# v0_4_2.net
KiCad netlist of a schematic drawn in EAGLE
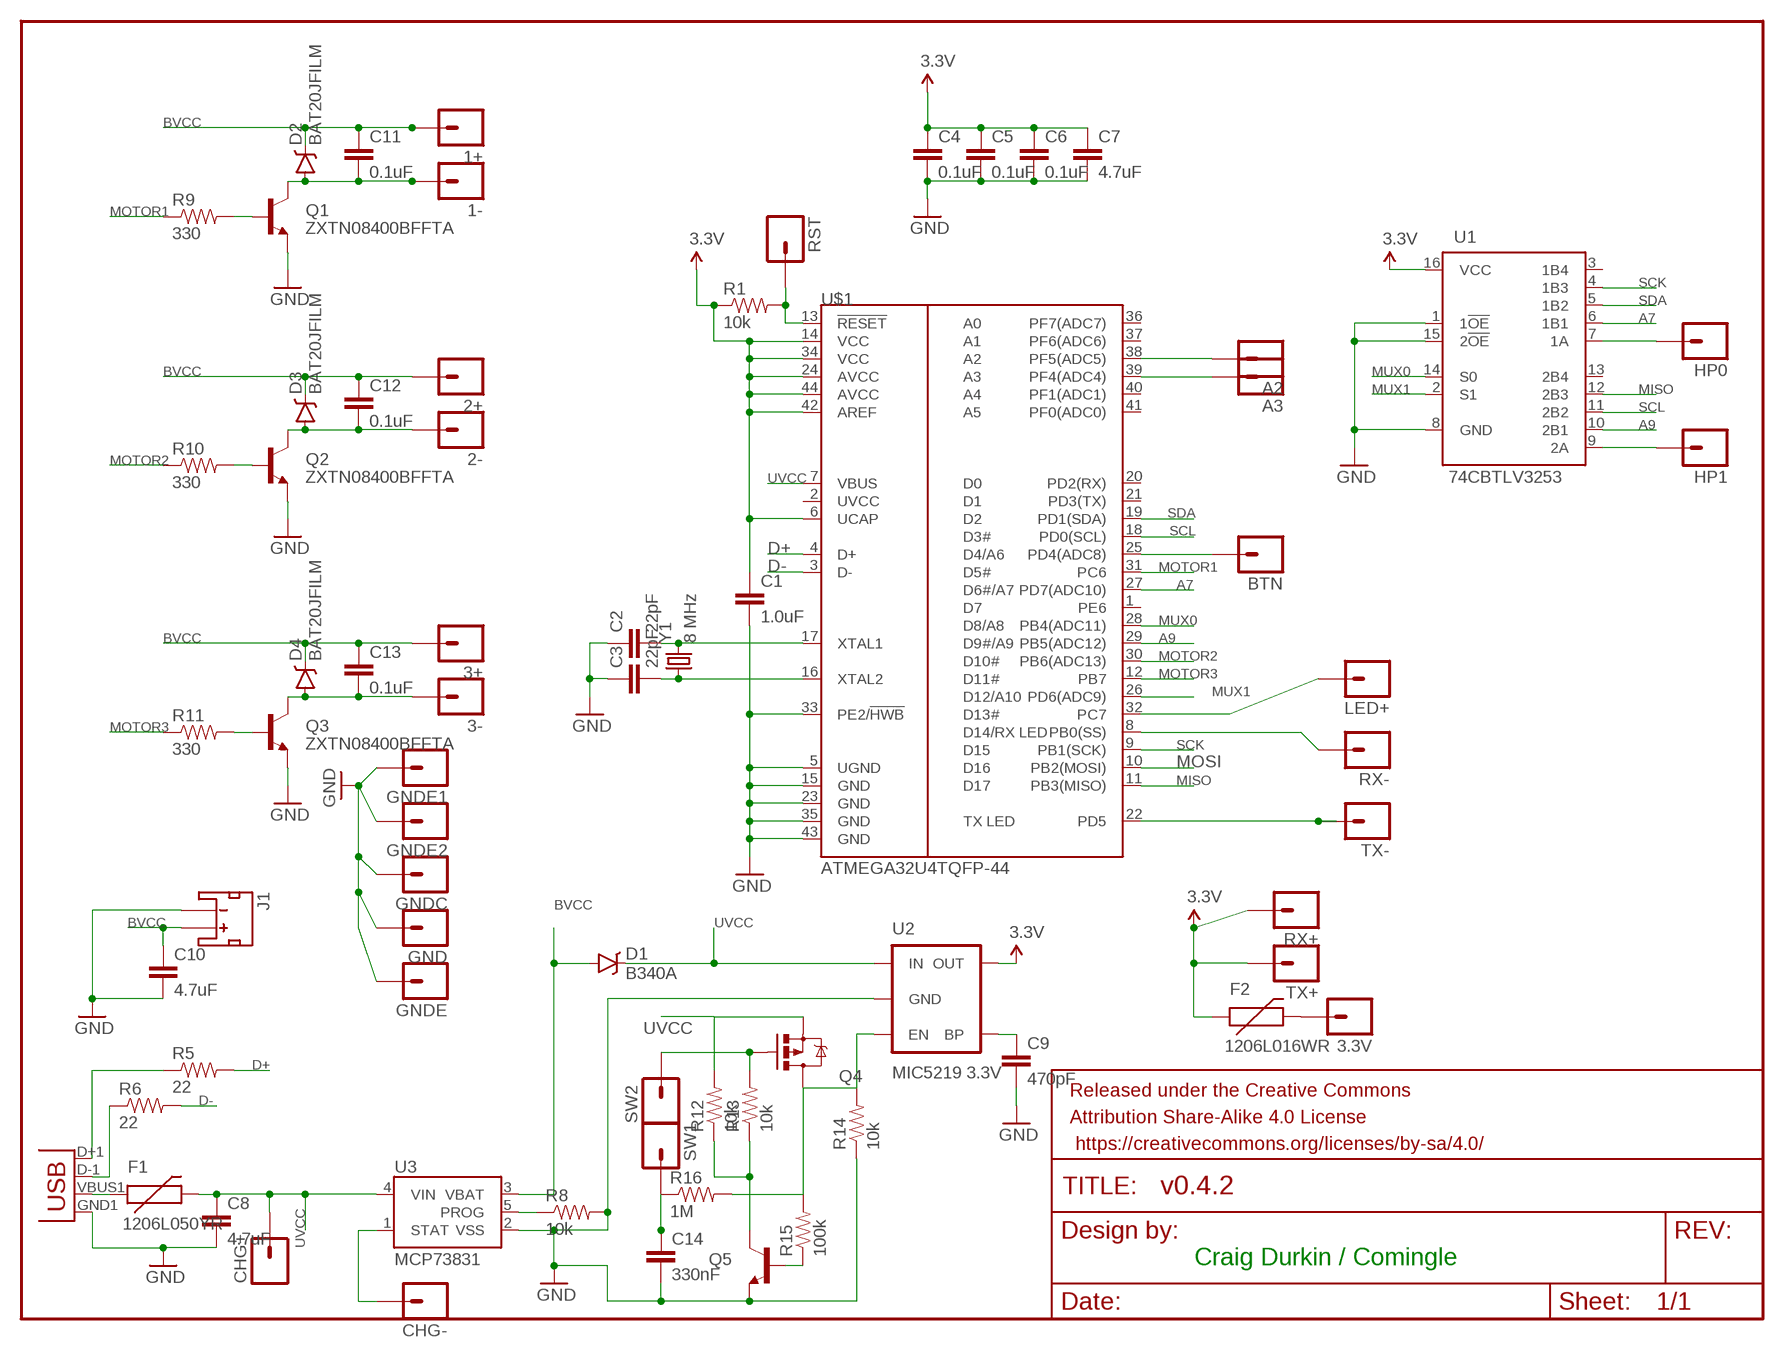
[diagram p0: schematic, sheet 1]

(export (version "E")
  (design (tool "Eeschema 10.0.6"))
  (components
    (comp (ref "1+")
      (value "M01PTH")
      (footprint "eagle-import:1X01")
      (libsource (lib "eagle-import") (part "M01PTH"))
    )
    (comp (ref "1-")
      (value "M01PTH")
      (footprint "eagle-import:1X01")
      (libsource (lib "eagle-import") (part "M01PTH"))
    )
    (comp (ref "2+")
      (value "M01PTH")
      (footprint "eagle-import:1X01")
      (libsource (lib "eagle-import") (part "M01PTH"))
    )
    (comp (ref "2-")
      (value "M01PTH")
      (footprint "eagle-import:1X01")
      (libsource (lib "eagle-import") (part "M01PTH"))
    )
    (comp (ref "3+")
      (value "M01PTH")
      (footprint "eagle-import:1X01")
      (libsource (lib "eagle-import") (part "M01PTH"))
    )
    (comp (ref "3-")
      (value "M01PTH")
      (footprint "eagle-import:1X01")
      (libsource (lib "eagle-import") (part "M01PTH"))
    )
    (comp (ref "3.3V")
      (value "M01PTH")
      (footprint "eagle-import:1X01")
      (libsource (lib "eagle-import") (part "M01PTH"))
    )
    (comp (ref "A2")
      (value "M01PTH")
      (footprint "eagle-import:1X01")
      (libsource (lib "eagle-import") (part "M01PTH"))
    )
    (comp (ref "A3")
      (value "M01PTH")
      (footprint "eagle-import:1X01")
      (libsource (lib "eagle-import") (part "M01PTH"))
    )
    (comp (ref "BTN")
      (value "M01PTH")
      (footprint "eagle-import:1X01")
      (libsource (lib "eagle-import") (part "M01PTH"))
    )
    (comp (ref "C1")
      (value "1.0uF")
      (footprint "eagle-import:0603-CAP")
      (libsource (lib "eagle-import") (part "CAP0603-CAP"))
    )
    (comp (ref "C2")
      (value "22pF")
      (footprint "eagle-import:0603-CAP")
      (libsource (lib "eagle-import") (part "CAP0603-CAP"))
    )
    (comp (ref "C3")
      (value "22pF")
      (footprint "eagle-import:0603-CAP")
      (libsource (lib "eagle-import") (part "CAP0603-CAP"))
    )
    (comp (ref "C4")
      (value "0.1uF")
      (footprint "eagle-import:0603-CAP")
      (libsource (lib "eagle-import") (part "SparkFun-Passives_CAP0603-CAP"))
    )
    (comp (ref "C5")
      (value "0.1uF")
      (footprint "eagle-import:0603-CAP")
      (libsource (lib "eagle-import") (part "SparkFun-Passives_CAP0603-CAP"))
    )
    (comp (ref "C6")
      (value "0.1uF")
      (footprint "eagle-import:0603-CAP")
      (libsource (lib "eagle-import") (part "SparkFun-Passives_CAP0603-CAP"))
    )
    (comp (ref "C7")
      (value "4.7uF")
      (footprint "eagle-import:0603-CAP")
      (libsource (lib "eagle-import") (part "SparkFun-Passives_CAP0603-CAP"))
    )
    (comp (ref "C8")
      (value "4.7uF")
      (footprint "eagle-import:1206")
      (libsource (lib "eagle-import") (part "SparkFun-Passives_CAP1206"))
    )
    (comp (ref "C9")
      (value "470pF")
      (footprint "eagle-import:0603-CAP")
      (libsource (lib "eagle-import") (part "CAP0603-CAP"))
    )
    (comp (ref "C10")
      (value "4.7uF")
      (footprint "eagle-import:1206")
      (libsource (lib "eagle-import") (part "SparkFun-Passives_CAP1206"))
    )
    (comp (ref "C11")
      (value "0.1uF")
      (footprint "eagle-import:0603-CAP")
      (libsource (lib "eagle-import") (part "CAP0603-CAP"))
    )
    (comp (ref "C12")
      (value "0.1uF")
      (footprint "eagle-import:0603-CAP")
      (libsource (lib "eagle-import") (part "CAP0603-CAP"))
    )
    (comp (ref "C13")
      (value "0.1uF")
      (footprint "eagle-import:0603-CAP")
      (libsource (lib "eagle-import") (part "CAP0603-CAP"))
    )
    (comp (ref "C14")
      (value "330nF")
      (footprint "eagle-import:0603-CAP")
      (libsource (lib "eagle-import") (part "CAP0603-CAP"))
    )
    (comp (ref "CHG+")
      (value "M01PTH")
      (footprint "eagle-import:1X01")
      (libsource (lib "eagle-import") (part "M01PTH"))
    )
    (comp (ref "CHG-")
      (value "M01PTH")
      (footprint "eagle-import:1X01")
      (libsource (lib "eagle-import") (part "M01PTH"))
    )
    (comp (ref "D1")
      (value "B340A")
      (footprint "eagle-import:SMA-DIODE")
      (libsource (lib "eagle-import") (part "DIODE-SCHOTTKY-B340A"))
    )
    (comp (ref "D2")
      (value "BAT20JFILM")
      (footprint "eagle-import:SOD-323")
      (libsource (lib "eagle-import") (part "BAT20JFILM"))
    )
    (comp (ref "D3")
      (value "BAT20JFILM")
      (footprint "eagle-import:SOD-323")
      (libsource (lib "eagle-import") (part "BAT20JFILM"))
    )
    (comp (ref "D4")
      (value "BAT20JFILM")
      (footprint "eagle-import:SOD-323")
      (libsource (lib "eagle-import") (part "BAT20JFILM"))
    )
    (comp (ref "F1")
      (value "1206L050YR")
      (footprint "eagle-import:PTC-1206")
      (libsource (lib "eagle-import") (part "PTCSMD"))
    )
    (comp (ref "F2")
      (value "1206L016WR")
      (footprint "eagle-import:PTC-1206")
      (libsource (lib "eagle-import") (part "PTCSMD"))
    )
    (comp (ref "FRAME1")
      (value "FRAME-LETTER")
      (footprint "eagle-import:CREATIVE_COMMONS")
      (libsource (lib "eagle-import") (part "FRAME-LETTER"))
    )
    (comp (ref "GND")
      (value "M01PTH")
      (footprint "eagle-import:1X01")
      (libsource (lib "eagle-import") (part "M01PTH"))
    )
    (comp (ref "GNDC")
      (value "M01PTH")
      (footprint "eagle-import:1X01")
      (libsource (lib "eagle-import") (part "M01PTH"))
    )
    (comp (ref "GNDE")
      (value "M01PTH")
      (footprint "eagle-import:1X01")
      (libsource (lib "eagle-import") (part "M01PTH"))
    )
    (comp (ref "GNDE1")
      (value "M01PTH")
      (footprint "eagle-import:1X01")
      (libsource (lib "eagle-import") (part "M01PTH"))
    )
    (comp (ref "GNDE2")
      (value "M01PTH")
      (footprint "eagle-import:1X01")
      (libsource (lib "eagle-import") (part "M01PTH"))
    )
    (comp (ref "HP0")
      (value "M01PTH")
      (footprint "eagle-import:1X01")
      (libsource (lib "eagle-import") (part "M01PTH"))
    )
    (comp (ref "HP1")
      (value "M01PTH")
      (footprint "eagle-import:1X01")
      (libsource (lib "eagle-import") (part "M01PTH"))
    )
    (comp (ref "J1")
      (value "JST_2MM_MALE")
      (footprint "eagle-import:JST-2-SMD")
      (libsource (lib "eagle-import") (part "JST_2MM_MALE"))
    )
    (comp (ref "JP4")
      (value "USB")
      (footprint "eagle-import:USB-B-MICRO-SMD_V03")
      (libsource (lib "eagle-import") (part "USB"))
    )
    (comp (ref "LED+")
      (value "M01PTH")
      (footprint "eagle-import:1X01")
      (libsource (lib "eagle-import") (part "M01PTH"))
    )
    (comp (ref "Q1")
      (value "ZXTN08400BFFTA")
      (footprint "eagle-import:SOT23-3")
      (libsource (lib "eagle-import") (part "TRANSISTOR_NPNSOT23-3"))
    )
    (comp (ref "Q2")
      (value "ZXTN08400BFFTA")
      (footprint "eagle-import:SOT23-3")
      (libsource (lib "eagle-import") (part "TRANSISTOR_NPNSOT23-3"))
    )
    (comp (ref "Q3")
      (value "ZXTN08400BFFTA")
      (footprint "eagle-import:SOT23-3")
      (libsource (lib "eagle-import") (part "TRANSISTOR_NPNSOT23-3"))
    )
    (comp (ref "Q4")
      (value "NTS2101PT1G")
      (footprint "eagle-import:SOT23-3")
      (libsource (lib "eagle-import") (part "MOSFET-PCHANNEL"))
    )
    (comp (ref "Q5")
      (value "MMBT2222A")
      (footprint "eagle-import:SOT23-3")
      (libsource (lib "eagle-import") (part "TRANSISTOR_NPNMMBT2222A"))
    )
    (comp (ref "R1")
      (value "10k")
      (footprint "eagle-import:0603-RES")
      (libsource (lib "eagle-import") (part "RESISTOR0603-RES"))
    )
    (comp (ref "R5")
      (value "22")
      (footprint "eagle-import:0603-RES")
      (libsource (lib "eagle-import") (part "RESISTOR0603-RES"))
    )
    (comp (ref "R6")
      (value "22")
      (footprint "eagle-import:0603-RES")
      (libsource (lib "eagle-import") (part "RESISTOR0603-RES"))
    )
    (comp (ref "R8")
      (value "10k")
      (footprint "eagle-import:0603-RES")
      (libsource (lib "eagle-import") (part "RESISTOR0603-RES"))
    )
    (comp (ref "R9")
      (value "330")
      (footprint "eagle-import:0603-RES")
      (libsource (lib "eagle-import") (part "RESISTOR0603-RES"))
    )
    (comp (ref "R10")
      (value "330")
      (footprint "eagle-import:0603-RES")
      (libsource (lib "eagle-import") (part "RESISTOR0603-RES"))
    )
    (comp (ref "R11")
      (value "330")
      (footprint "eagle-import:0603-RES")
      (libsource (lib "eagle-import") (part "RESISTOR0603-RES"))
    )
    (comp (ref "R12")
      (value "10k")
      (footprint "eagle-import:0603-RES")
      (libsource (lib "eagle-import") (part "RESISTOR0603-RES"))
    )
    (comp (ref "R13")
      (value "10k")
      (footprint "eagle-import:0603-RES")
      (libsource (lib "eagle-import") (part "RESISTOR0603-RES"))
    )
    (comp (ref "R14")
      (value "10k")
      (footprint "eagle-import:0603-RES")
      (libsource (lib "eagle-import") (part "RESISTOR0603-RES"))
    )
    (comp (ref "R15")
      (value "100k")
      (footprint "eagle-import:0603-RES")
      (libsource (lib "eagle-import") (part "RESISTOR0603-RES"))
    )
    (comp (ref "R16")
      (value "1M")
      (footprint "eagle-import:0603-RES")
      (libsource (lib "eagle-import") (part "RESISTOR0603-RES"))
    )
    (comp (ref "RST")
      (value "M01PTH")
      (footprint "eagle-import:1X01")
      (libsource (lib "eagle-import") (part "M01PTH"))
    )
    (comp (ref "RX+")
      (value "M01PTH")
      (footprint "eagle-import:1X01")
      (libsource (lib "eagle-import") (part "M01PTH"))
    )
    (comp (ref "RX-")
      (value "M01PTH")
      (footprint "eagle-import:1X01")
      (libsource (lib "eagle-import") (part "M01PTH"))
    )
    (comp (ref "SW1")
      (value "M01PTH")
      (footprint "eagle-import:1X01")
      (libsource (lib "eagle-import") (part "M01PTH"))
    )
    (comp (ref "SW2")
      (value "M01PTH")
      (footprint "eagle-import:1X01")
      (libsource (lib "eagle-import") (part "M01PTH"))
    )
    (comp (ref "TX+")
      (value "M01PTH")
      (footprint "eagle-import:1X01")
      (libsource (lib "eagle-import") (part "M01PTH"))
    )
    (comp (ref "TX-")
      (value "M01PTH")
      (footprint "eagle-import:1X01")
      (libsource (lib "eagle-import") (part "M01PTH"))
    )
    (comp (ref "U$1")
      (value "ATMEGA32U4TQFP-44")
      (footprint "eagle-import:TQFP44")
      (libsource (lib "eagle-import") (part "ATMEGA32U4TQFP-44"))
    )
    (comp (ref "U1")
      (value "74CBTLV3253")
      (footprint "eagle-import:SSOP16-PRACTICE")
      (libsource (lib "eagle-import") (part "74CBTLV3253"))
    )
    (comp (ref "U2")
      (value "MIC5219 3.3V")
      (footprint "eagle-import:SOT23-5")
      (libsource (lib "eagle-import") (part "V_REG_MIC52193.3V"))
    )
    (comp (ref "U3")
      (value "MCP73831")
      (footprint "eagle-import:SOT23-5")
      (libsource (lib "eagle-import") (part "MCP73831"))
    )
    (comp (ref "Y1")
      (value "8 MHz")
      (footprint "eagle-import:CRYSTAL-SMD-5X3")
      (libsource (lib "eagle-import") (part "CRYSTAL5X3"))
    )
  )
  (nets
    (net (code "1") (name "/A7") (class "Default")
      (node (ref "U$1") (pin "27") (pinfunction "PD7(ADC10)_27") (pintype "bidirectional"))
      (node (ref "U1") (pin "6") (pinfunction "1B1_6") (pintype "bidirectional"))
    )
    (net (code "2") (name "/A9") (class "Default")
      (node (ref "U$1") (pin "29") (pinfunction "PB5(ADC12)_29") (pintype "bidirectional"))
      (node (ref "U1") (pin "10") (pinfunction "2B1_10") (pintype "bidirectional"))
    )
    (net (code "3") (name "/BVCC") (class "Default")
      (node (ref "1+") (pin "1") (pinfunction "1_1") (pintype "passive"))
      (node (ref "2+") (pin "1") (pinfunction "1_1") (pintype "passive"))
      (node (ref "3+") (pin "1") (pinfunction "1_1") (pintype "passive"))
      (node (ref "C10") (pin "1") (pinfunction "1_1") (pintype "passive"))
      (node (ref "C11") (pin "1") (pinfunction "1_1") (pintype "passive"))
      (node (ref "C12") (pin "1") (pinfunction "1_1") (pintype "passive"))
      (node (ref "C13") (pin "1") (pinfunction "1_1") (pintype "passive"))
      (node (ref "D1") (pin "A") (pinfunction "A_A") (pintype "passive"))
      (node (ref "D2") (pin "C") (pinfunction "C_C") (pintype "passive"))
      (node (ref "D3") (pin "C") (pinfunction "C_C") (pintype "passive"))
      (node (ref "D4") (pin "C") (pinfunction "C_C") (pintype "passive"))
      (node (ref "J1") (pin "2") (pinfunction "+_2") (pintype "bidirectional"))
      (node (ref "U3") (pin "3") (pinfunction "VBAT_3") (pintype "power_in"))
    )
    (net (code "4") (name "/D+") (class "Default")
      (node (ref "R5") (pin "2") (pinfunction "2_2") (pintype "passive"))
      (node (ref "U$1") (pin "4") (pinfunction "D+_4") (pintype "bidirectional"))
    )
    (net (code "5") (name "/D-") (class "Default")
      (node (ref "R6") (pin "2") (pinfunction "2_2") (pintype "passive"))
      (node (ref "U$1") (pin "3") (pinfunction "D-_3") (pintype "bidirectional"))
    )
    (net (code "6") (name "/MISO") (class "Default")
      (node (ref "U$1") (pin "11") (pinfunction "PB3(MISO)_11") (pintype "bidirectional"))
      (node (ref "U1") (pin "12") (pinfunction "2B3_12") (pintype "bidirectional"))
    )
    (net (code "7") (name "/MOSI") (class "Default")
      (node (ref "U$1") (pin "10") (pinfunction "PB2(MOSI)_10") (pintype "bidirectional"))
    )
    (net (code "8") (name "/MOTOR1") (class "Default")
      (node (ref "R9") (pin "1") (pinfunction "1_1") (pintype "passive"))
      (node (ref "U$1") (pin "31") (pinfunction "PC6_31") (pintype "bidirectional"))
    )
    (net (code "9") (name "/MOTOR2") (class "Default")
      (node (ref "R10") (pin "1") (pinfunction "1_1") (pintype "passive"))
      (node (ref "U$1") (pin "30") (pinfunction "PB6(ADC13)_30") (pintype "bidirectional"))
    )
    (net (code "10") (name "/MOTOR3") (class "Default")
      (node (ref "R11") (pin "1") (pinfunction "1_1") (pintype "passive"))
      (node (ref "U$1") (pin "12") (pinfunction "PB7_12") (pintype "bidirectional"))
    )
    (net (code "11") (name "/MUX0") (class "Default")
      (node (ref "U$1") (pin "28") (pinfunction "PB4(ADC11)_28") (pintype "bidirectional"))
      (node (ref "U1") (pin "14") (pinfunction "S0_14") (pintype "bidirectional"))
    )
    (net (code "12") (name "/MUX1") (class "Default")
      (node (ref "U$1") (pin "26") (pinfunction "PD6(ADC9)_26") (pintype "bidirectional"))
      (node (ref "U1") (pin "2") (pinfunction "S1_2") (pintype "bidirectional"))
    )
    (net (code "13") (name "/SCK") (class "Default")
      (node (ref "U$1") (pin "9") (pinfunction "PB1(SCK)_9") (pintype "bidirectional"))
      (node (ref "U1") (pin "4") (pinfunction "1B3_4") (pintype "bidirectional"))
    )
    (net (code "14") (name "/SCL") (class "Default")
      (node (ref "U$1") (pin "18") (pinfunction "PD0(SCL)_18") (pintype "bidirectional"))
      (node (ref "U1") (pin "11") (pinfunction "2B2_11") (pintype "bidirectional"))
    )
    (net (code "15") (name "/SDA") (class "Default")
      (node (ref "U$1") (pin "19") (pinfunction "PD1(SDA)_19") (pintype "bidirectional"))
      (node (ref "U1") (pin "5") (pinfunction "1B2_5") (pintype "bidirectional"))
    )
    (net (code "16") (name "/UVCC") (class "Default")
      (node (ref "C8") (pin "1") (pinfunction "1_1") (pintype "passive"))
      (node (ref "CHG+") (pin "1") (pinfunction "1_1") (pintype "passive"))
      (node (ref "D1") (pin "C") (pinfunction "C_C") (pintype "passive"))
      (node (ref "F1") (pin "2") (pinfunction "2_2") (pintype "bidirectional"))
      (node (ref "Q4") (pin "2") (pinfunction "S_2") (pintype "passive"))
      (node (ref "R12") (pin "2") (pinfunction "2_2") (pintype "passive"))
      (node (ref "U$1") (pin "7") (pinfunction "VBUS_7") (pintype "bidirectional"))
      (node (ref "U2") (pin "1") (pinfunction "IN_1") (pintype "input"))
      (node (ref "U3") (pin "4") (pinfunction "VIN_4") (pintype "power_in"))
    )
    (net (code "17") (name "3.3V") (class "Default")
      (node (ref "C1") (pin "1") (pinfunction "1_1") (pintype "passive"))
      (node (ref "C4") (pin "1") (pinfunction "1_1") (pintype "passive"))
      (node (ref "C5") (pin "1") (pinfunction "1_1") (pintype "passive"))
      (node (ref "C6") (pin "1") (pinfunction "1_1") (pintype "passive"))
      (node (ref "C7") (pin "1") (pinfunction "1_1") (pintype "passive"))
      (node (ref "F2") (pin "1") (pinfunction "1_1") (pintype "bidirectional"))
      (node (ref "R1") (pin "1") (pinfunction "1_1") (pintype "passive"))
      (node (ref "RX+") (pin "1") (pinfunction "1_1") (pintype "passive"))
      (node (ref "TX+") (pin "1") (pinfunction "1_1") (pintype "passive"))
      (node (ref "U$1") (pin "14") (pinfunction "VCC_14") (pintype "bidirectional"))
      (node (ref "U$1") (pin "24") (pinfunction "AVCC_24") (pintype "bidirectional"))
      (node (ref "U$1") (pin "34") (pinfunction "VCC_34") (pintype "bidirectional"))
      (node (ref "U$1") (pin "42") (pinfunction "AREF_42") (pintype "bidirectional"))
      (node (ref "U$1") (pin "44") (pinfunction "AVCC_44") (pintype "bidirectional"))
      (node (ref "U$1") (pin "6") (pinfunction "UCAP_6") (pintype "bidirectional"))
      (node (ref "U1") (pin "16") (pinfunction "VCC_16") (pintype "power_in"))
      (node (ref "U2") (pin "5") (pinfunction "OUT_5") (pintype "passive"))
    )
    (net (code "18") (name "GND") (class "Default")
      (node (ref "C1") (pin "2") (pinfunction "2_2") (pintype "passive"))
      (node (ref "C10") (pin "2") (pinfunction "2_2") (pintype "passive"))
      (node (ref "C14") (pin "2") (pinfunction "2_2") (pintype "passive"))
      (node (ref "C2") (pin "1") (pinfunction "1_1") (pintype "passive"))
      (node (ref "C3") (pin "1") (pinfunction "1_1") (pintype "passive"))
      (node (ref "C4") (pin "2") (pinfunction "2_2") (pintype "passive"))
      (node (ref "C5") (pin "2") (pinfunction "2_2") (pintype "passive"))
      (node (ref "C6") (pin "2") (pinfunction "2_2") (pintype "passive"))
      (node (ref "C7") (pin "2") (pinfunction "2_2") (pintype "passive"))
      (node (ref "C8") (pin "2") (pinfunction "2_2") (pintype "passive"))
      (node (ref "C9") (pin "2") (pinfunction "2_2") (pintype "passive"))
      (node (ref "GND") (pin "1") (pinfunction "1_1") (pintype "passive"))
      (node (ref "GNDC") (pin "1") (pinfunction "1_1") (pintype "passive"))
      (node (ref "GNDE") (pin "1") (pinfunction "1_1") (pintype "passive"))
      (node (ref "GNDE1") (pin "1") (pinfunction "1_1") (pintype "passive"))
      (node (ref "GNDE2") (pin "1") (pinfunction "1_1") (pintype "passive"))
      (node (ref "J1") (pin "1") (pinfunction "-_1") (pintype "bidirectional"))
      (node (ref "JP4") (pin "GND1") (pinfunction "GND_GND1") (pintype "bidirectional"))
      (node (ref "Q1") (pin "2") (pinfunction "E_2") (pintype "passive"))
      (node (ref "Q2") (pin "2") (pinfunction "E_2") (pintype "passive"))
      (node (ref "Q3") (pin "2") (pinfunction "E_2") (pintype "passive"))
      (node (ref "Q5") (pin "2") (pinfunction "E_2") (pintype "passive"))
      (node (ref "R14") (pin "1") (pinfunction "1_1") (pintype "passive"))
      (node (ref "R8") (pin "2") (pinfunction "2_2") (pintype "passive"))
      (node (ref "U$1") (pin "15") (pinfunction "GND_15") (pintype "bidirectional"))
      (node (ref "U$1") (pin "23") (pinfunction "GND_23") (pintype "bidirectional"))
      (node (ref "U$1") (pin "33") (pinfunction "PE2/~{HWB}_33") (pintype "bidirectional"))
      (node (ref "U$1") (pin "35") (pinfunction "GND_35") (pintype "bidirectional"))
      (node (ref "U$1") (pin "43") (pinfunction "GND_43") (pintype "bidirectional"))
      (node (ref "U$1") (pin "5") (pinfunction "UGND_5") (pintype "bidirectional"))
      (node (ref "U1") (pin "1") (pinfunction "1~{OE}_1") (pintype "input"))
      (node (ref "U1") (pin "15") (pinfunction "2~{OE}_15") (pintype "input"))
      (node (ref "U1") (pin "8") (pinfunction "GND_8") (pintype "power_in"))
      (node (ref "U2") (pin "2") (pinfunction "GND_2") (pintype "input"))
      (node (ref "U3") (pin "2") (pinfunction "VSS_2") (pintype "power_in"))
    )
    (net (code "19") (name "Net-(3.3V-Pad1)") (class "Default")
      (node (ref "3.3V") (pin "1") (pinfunction "1_1") (pintype "passive"))
      (node (ref "F2") (pin "2") (pinfunction "2_2") (pintype "bidirectional"))
    )
    (net (code "20") (name "Net-(C14-Pad1)") (class "Default")
      (node (ref "C14") (pin "1") (pinfunction "1_1") (pintype "passive"))
      (node (ref "R16") (pin "1") (pinfunction "1_1") (pintype "passive"))
      (node (ref "SW1") (pin "1") (pinfunction "1_1") (pintype "passive"))
    )
    (net (code "21") (name "Net-(JP4-D+)") (class "Default")
      (node (ref "JP4") (pin "D+1") (pinfunction "D+_D+1") (pintype "bidirectional"))
      (node (ref "R5") (pin "1") (pinfunction "1_1") (pintype "passive"))
    )
    (net (code "22") (name "Net-(JP4-D-)") (class "Default")
      (node (ref "JP4") (pin "D-1") (pinfunction "D-_D-1") (pintype "bidirectional"))
      (node (ref "R6") (pin "1") (pinfunction "1_1") (pintype "passive"))
    )
    (net (code "23") (name "Net-(JP4-VBUS)") (class "Default")
      (node (ref "F1") (pin "1") (pinfunction "1_1") (pintype "bidirectional"))
      (node (ref "JP4") (pin "VBUS1") (pinfunction "VBUS_VBUS1") (pintype "bidirectional"))
    )
    (net (code "24") (name "Net-(Q1-B)") (class "Default")
      (node (ref "Q1") (pin "1") (pinfunction "B_1") (pintype "passive"))
      (node (ref "R9") (pin "2") (pinfunction "2_2") (pintype "passive"))
    )
    (net (code "25") (name "Net-(Q1-C)") (class "Default")
      (node (ref "1-") (pin "1") (pinfunction "1_1") (pintype "passive"))
      (node (ref "C11") (pin "2") (pinfunction "2_2") (pintype "passive"))
      (node (ref "D2") (pin "A") (pinfunction "A_A") (pintype "passive"))
      (node (ref "Q1") (pin "3") (pinfunction "C_3") (pintype "passive"))
    )
    (net (code "26") (name "Net-(Q2-B)") (class "Default")
      (node (ref "Q2") (pin "1") (pinfunction "B_1") (pintype "passive"))
      (node (ref "R10") (pin "2") (pinfunction "2_2") (pintype "passive"))
    )
    (net (code "27") (name "Net-(Q2-C)") (class "Default")
      (node (ref "2-") (pin "1") (pinfunction "1_1") (pintype "passive"))
      (node (ref "C12") (pin "2") (pinfunction "2_2") (pintype "passive"))
      (node (ref "D3") (pin "A") (pinfunction "A_A") (pintype "passive"))
      (node (ref "Q2") (pin "3") (pinfunction "C_3") (pintype "passive"))
    )
    (net (code "28") (name "Net-(Q3-B)") (class "Default")
      (node (ref "Q3") (pin "1") (pinfunction "B_1") (pintype "passive"))
      (node (ref "R11") (pin "2") (pinfunction "2_2") (pintype "passive"))
    )
    (net (code "29") (name "Net-(Q3-C)") (class "Default")
      (node (ref "3-") (pin "1") (pinfunction "1_1") (pintype "passive"))
      (node (ref "C13") (pin "2") (pinfunction "2_2") (pintype "passive"))
      (node (ref "D4") (pin "A") (pinfunction "A_A") (pintype "passive"))
      (node (ref "Q3") (pin "3") (pinfunction "C_3") (pintype "passive"))
    )
    (net (code "30") (name "Net-(Q4-D)") (class "Default")
      (node (ref "Q4") (pin "3") (pinfunction "D_3") (pintype "passive"))
      (node (ref "R14") (pin "2") (pinfunction "2_2") (pintype "passive"))
      (node (ref "R15") (pin "2") (pinfunction "2_2") (pintype "passive"))
      (node (ref "R16") (pin "2") (pinfunction "2_2") (pintype "passive"))
      (node (ref "U2") (pin "3") (pinfunction "EN_3") (pintype "input"))
    )
    (net (code "31") (name "Net-(Q4-G)") (class "Default")
      (node (ref "Q4") (pin "1") (pinfunction "G_1") (pintype "passive"))
      (node (ref "R13") (pin "2") (pinfunction "2_2") (pintype "passive"))
      (node (ref "SW2") (pin "1") (pinfunction "1_1") (pintype "passive"))
    )
    (net (code "32") (name "Net-(Q5-B)") (class "Default")
      (node (ref "Q5") (pin "1") (pinfunction "B_1") (pintype "passive"))
      (node (ref "R15") (pin "1") (pinfunction "1_1") (pintype "passive"))
    )
    (net (code "33") (name "Net-(Q5-C)") (class "Default")
      (node (ref "Q5") (pin "3") (pinfunction "C_3") (pintype "passive"))
      (node (ref "R12") (pin "1") (pinfunction "1_1") (pintype "passive"))
      (node (ref "R13") (pin "1") (pinfunction "1_1") (pintype "passive"))
    )
    (net (code "34") (name "Net-(U$1-PB0(SS))") (class "Default")
      (node (ref "RX-") (pin "1") (pinfunction "1_1") (pintype "passive"))
      (node (ref "U$1") (pin "8") (pinfunction "PB0(SS)_8") (pintype "bidirectional"))
    )
    (net (code "35") (name "Net-(U$1-PC7)") (class "Default")
      (node (ref "LED+") (pin "1") (pinfunction "1_1") (pintype "passive"))
      (node (ref "U$1") (pin "32") (pinfunction "PC7_32") (pintype "bidirectional"))
    )
    (net (code "36") (name "Net-(U$1-PD4(ADC8))") (class "Default")
      (node (ref "BTN") (pin "1") (pinfunction "1_1") (pintype "passive"))
      (node (ref "U$1") (pin "25") (pinfunction "PD4(ADC8)_25") (pintype "bidirectional"))
    )
    (net (code "37") (name "Net-(U$1-PD5)") (class "Default")
      (node (ref "TX-") (pin "1") (pinfunction "1_1") (pintype "passive"))
      (node (ref "U$1") (pin "22") (pinfunction "PD5_22") (pintype "bidirectional"))
    )
    (net (code "38") (name "Net-(U$1-PF4(ADC4))") (class "Default")
      (node (ref "A3") (pin "1") (pinfunction "1_1") (pintype "passive"))
      (node (ref "U$1") (pin "39") (pinfunction "PF4(ADC4)_39") (pintype "bidirectional"))
    )
    (net (code "39") (name "Net-(U$1-PF5(ADC5))") (class "Default")
      (node (ref "A2") (pin "1") (pinfunction "1_1") (pintype "passive"))
      (node (ref "U$1") (pin "38") (pinfunction "PF5(ADC5)_38") (pintype "bidirectional"))
    )
    (net (code "40") (name "Net-(U$1-XTAL1)") (class "Default")
      (node (ref "C2") (pin "2") (pinfunction "2_2") (pintype "passive"))
      (node (ref "U$1") (pin "17") (pinfunction "XTAL1_17") (pintype "bidirectional"))
      (node (ref "Y1") (pin "3") (pinfunction "2_3") (pintype "passive"))
    )
    (net (code "41") (name "Net-(U$1-XTAL2)") (class "Default")
      (node (ref "C3") (pin "2") (pinfunction "2_2") (pintype "passive"))
      (node (ref "U$1") (pin "16") (pinfunction "XTAL2_16") (pintype "bidirectional"))
      (node (ref "Y1") (pin "1") (pinfunction "1_1") (pintype "passive"))
    )
    (net (code "42") (name "Net-(U$1-~{RESET})") (class "Default")
      (node (ref "R1") (pin "2") (pinfunction "2_2") (pintype "passive"))
      (node (ref "RST") (pin "1") (pinfunction "1_1") (pintype "passive"))
      (node (ref "U$1") (pin "13") (pinfunction "~{RESET}_13") (pintype "bidirectional"))
    )
    (net (code "43") (name "Net-(U1-1A)") (class "Default")
      (node (ref "HP0") (pin "1") (pinfunction "1_1") (pintype "passive"))
      (node (ref "U1") (pin "7") (pinfunction "1A_7") (pintype "bidirectional"))
    )
    (net (code "44") (name "Net-(U1-2A)") (class "Default")
      (node (ref "HP1") (pin "1") (pinfunction "1_1") (pintype "passive"))
      (node (ref "U1") (pin "9") (pinfunction "2A_9") (pintype "bidirectional"))
    )
    (net (code "45") (name "Net-(U2-BP)") (class "Default")
      (node (ref "C9") (pin "1") (pinfunction "1_1") (pintype "passive"))
      (node (ref "U2") (pin "4") (pinfunction "BP_4") (pintype "input"))
    )
    (net (code "46") (name "Net-(U3-PROG)") (class "Default")
      (node (ref "R8") (pin "1") (pinfunction "1_1") (pintype "passive"))
      (node (ref "U3") (pin "5") (pinfunction "PROG_5") (pintype "bidirectional"))
    )
    (net (code "47") (name "Net-(U3-STAT)") (class "Default")
      (node (ref "CHG-") (pin "1") (pinfunction "1_1") (pintype "passive"))
      (node (ref "U3") (pin "1") (pinfunction "STAT_1") (pintype "output"))
    )
    (net (code "48") (name "unconnected-(J1-PAD1-PadNC1)") (class "Default")
      (node (ref "J1") (pin "NC1") (pinfunction "PAD1_NC1") (pintype "bidirectional"))
    )
    (net (code "49") (name "unconnected-(J1-PAD2-PadNC2)") (class "Default")
      (node (ref "J1") (pin "NC2") (pinfunction "PAD2_NC2") (pintype "bidirectional"))
    )
    (net (code "50") (name "unconnected-(U$1-PD2(RX)-Pad20)") (class "Default")
      (node (ref "U$1") (pin "20") (pinfunction "PD2(RX)_20") (pintype "bidirectional"))
    )
    (net (code "51") (name "unconnected-(U$1-PD3(TX)-Pad21)") (class "Default")
      (node (ref "U$1") (pin "21") (pinfunction "PD3(TX)_21") (pintype "bidirectional"))
    )
    (net (code "52") (name "unconnected-(U$1-PE6-Pad1)") (class "Default")
      (node (ref "U$1") (pin "1") (pinfunction "PE6_1") (pintype "bidirectional"))
    )
    (net (code "53") (name "unconnected-(U$1-PF0(ADC0)-Pad41)") (class "Default")
      (node (ref "U$1") (pin "41") (pinfunction "PF0(ADC0)_41") (pintype "bidirectional"))
    )
    (net (code "54") (name "unconnected-(U$1-PF1(ADC1)-Pad40)") (class "Default")
      (node (ref "U$1") (pin "40") (pinfunction "PF1(ADC1)_40") (pintype "bidirectional"))
    )
    (net (code "55") (name "unconnected-(U$1-PF6(ADC6)-Pad37)") (class "Default")
      (node (ref "U$1") (pin "37") (pinfunction "PF6(ADC6)_37") (pintype "bidirectional"))
    )
    (net (code "56") (name "unconnected-(U$1-PF7(ADC7)-Pad36)") (class "Default")
      (node (ref "U$1") (pin "36") (pinfunction "PF7(ADC7)_36") (pintype "bidirectional"))
    )
    (net (code "57") (name "unconnected-(U$1-UVCC-Pad2)") (class "Default")
      (node (ref "U$1") (pin "2") (pinfunction "UVCC_2") (pintype "bidirectional"))
    )
    (net (code "58") (name "unconnected-(U1-1B4-Pad3)") (class "Default")
      (node (ref "U1") (pin "3") (pinfunction "1B4_3") (pintype "bidirectional"))
    )
    (net (code "59") (name "unconnected-(U1-2B4-Pad13)") (class "Default")
      (node (ref "U1") (pin "13") (pinfunction "2B4_13") (pintype "bidirectional"))
    )
  )
)
